# Top.net
KiCad netlist of a schematic drawn in Altium Designer
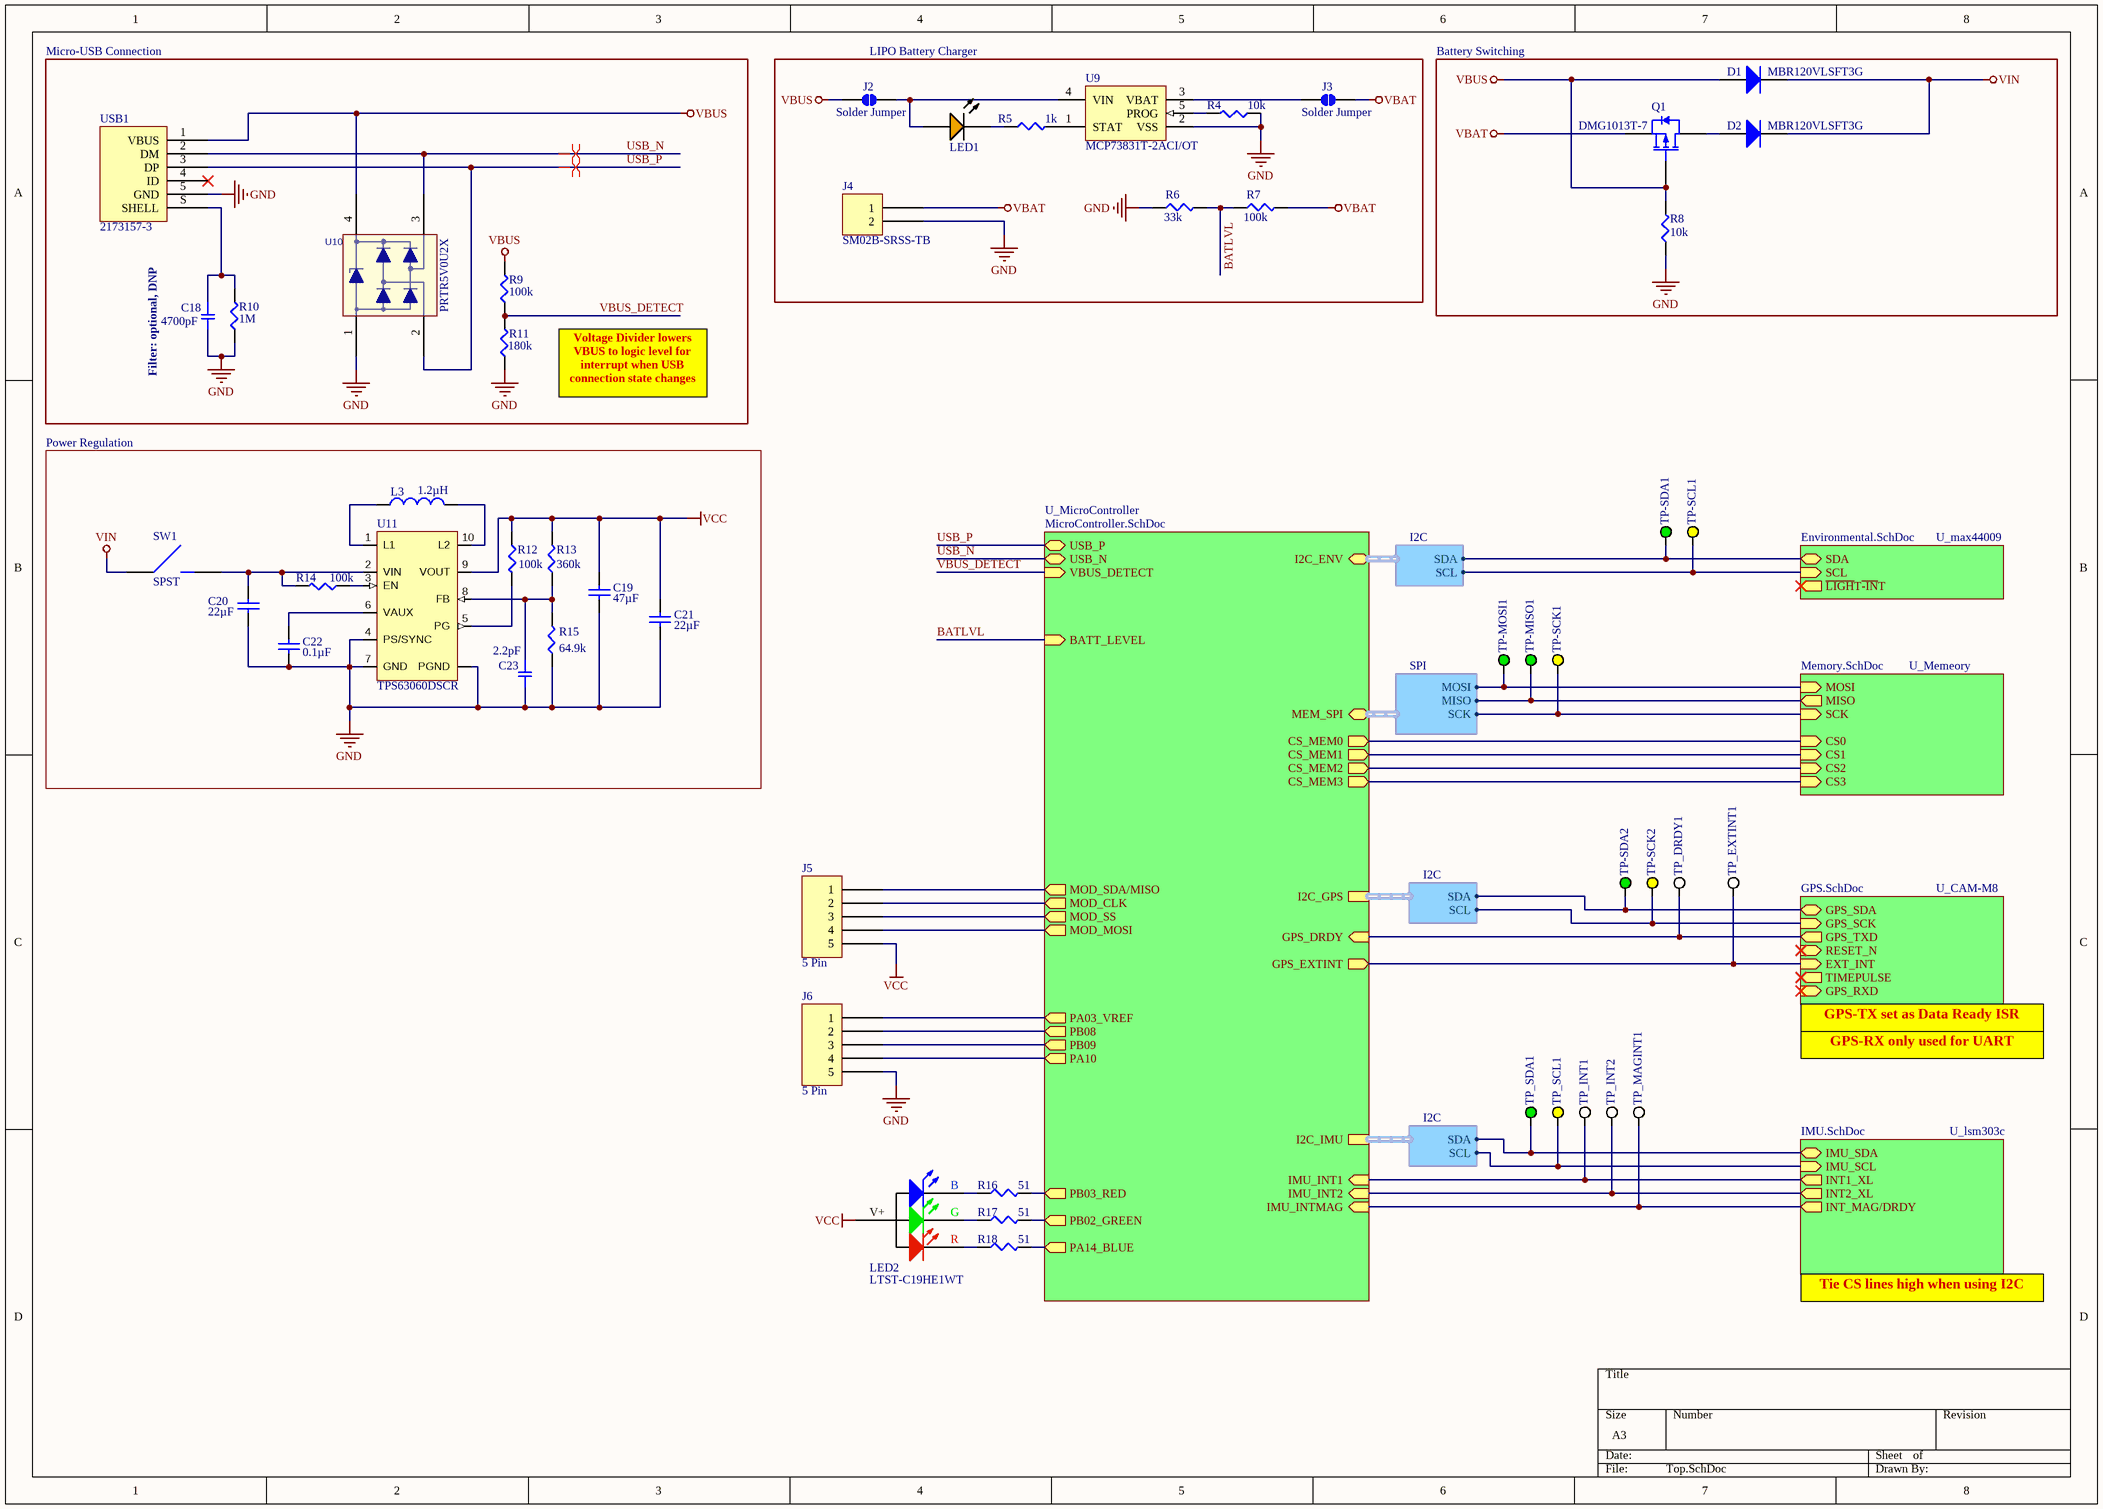
[diagram p0: Top.SchDoc]

(export (version "E")
  (design (tool "Eeschema 10.0.6"))
  (components
    (comp (ref "C18")
      (value "4700pF")
      (footprint "SMD-0603C")
      (description "CAP CER 4700PF 100V X7R 0603")
      (fields
        (field (name "DIGI-KEY PART NUMBER") "490-4930-1-ND")
        (field (name "PART NUMBER") "GCM188R72A472KA37D")
      )
      (libsource (lib "capacitor_murata_0603") (part "GCM188R72A472KA37D"))
    )
    (comp (ref "C19")
      (value "CL21A476MQCLRNC")
      (footprint "C0603N")
      (fields
        (field (name "HOUSEPART") "NO")
        (field (name "TOLERANCE") "±20%")
        (field (name "VOLTAGE") "6.3V")
        (field (name "CAPACITANCE") "47µF")
      )
      (libsource (lib "MF_Passives") (part "CAPACITOR_NP"))
    )
    (comp (ref "C20")
      (value "CL21A226MQCLQNC")
      (footprint "C0603N")
      (fields
        (field (name "HOUSEPART") "NO")
        (field (name "TOLERANCE") "±20%")
        (field (name "VOLTAGE") "6.3V")
        (field (name "CAPACITANCE") "22µF")
      )
      (libsource (lib "MF_Passives") (part "CAPACITOR_NP"))
    )
    (comp (ref "C21")
      (value "CL21A226MQCLQNC")
      (footprint "C0603N")
      (fields
        (field (name "HOUSEPART") "NO")
        (field (name "TOLERANCE") "±20%")
        (field (name "VOLTAGE") "6.3V")
        (field (name "CAPACITANCE") "22µF")
      )
      (libsource (lib "MF_Passives") (part "CAPACITOR_NP"))
    )
    (comp (ref "C22")
      (value "CL10B104KO8NFNC")
      (footprint "C0603N")
      (fields
        (field (name "HOUSEPART") "NO")
        (field (name "TOLERANCE") "±10%")
        (field (name "VOLTAGE") "16V")
        (field (name "CAPACITANCE") "0.1µF")
      )
      (libsource (lib "MF_Passives") (part "CAPACITOR_NP"))
    )
    (comp (ref "C23")
      (value "2.2pF")
      (footprint "SMD-0603C")
      (description "CAP CER 2.2PF 50V NP0 0603")
      (fields
        (field (name "DIGI-KEY PART NUMBER") "490-12719-1-ND")
        (field (name "PART NUMBER") "GRM1885C1H2R2BA01D")
      )
      (libsource (lib "capacitor_murata_0603") (part "GRM1885C1H2R2BA01D"))
    )
    (comp (ref "D1")
      (value "MBR120VLSFT3G")
      (footprint "MBR120VLSFT3G")
      (description "Diode Schottky 20V 1A Surface Mount SOD-123FL")
      (libsource (lib "OnSemi") (part "MBR120VLSFT3G"))
    )
    (comp (ref "D2")
      (value "MBR120VLSFT3G")
      (footprint "MBR120VLSFT3G")
      (description "Diode Schottky 20V 1A Surface Mount SOD-123FL")
      (libsource (lib "OnSemi") (part "MBR120VLSFT3G"))
    )
    (comp (ref "J2")
      (value "Solder Jumper")
      (footprint "Jumper_1.5x3")
      (libsource (lib "jumpers") (part "solderJumper"))
    )
    (comp (ref "J3")
      (value "Solder Jumper")
      (footprint "Jumper_1.5x3")
      (libsource (lib "jumpers") (part "solderJumper"))
    )
    (comp (ref "J4")
      (value "SM02B-SRSS-TB")
      (footprint "JST SM02B-SRSS-TB")
      (libsource (lib "Connectors") (part "2 Pin"))
    )
    (comp (ref "J5")
      (value "5 Pin")
      (footprint "PINHEAD127_1x5")
      (libsource (lib "Connectors") (part "5 Pin"))
    )
    (comp (ref "J6")
      (value "5 Pin")
      (footprint "PINHEAD127_1x5")
      (libsource (lib "Connectors") (part "5 Pin"))
    )
    (comp (ref "L3")
      (value "SRP4020-1R2M")
      (footprint "IND_BOURNS_SRP40")
      (fields (field (name "TOLERANCE") "±20%") (field (name "INDUCTANCE") "1.2µH"))
      (libsource (lib "Bourns") (part "SRP4020-1R2M"))
    )
    (comp (ref "LED1")
      (value "LTST-C190KFKT")
      (footprint "LED_0603")
      (description "LED Uni-Color Orange, 75 mW, 30 mA")
      (libsource (lib "Lite-On") (part "CMP-1544850-3"))
    )
    (comp (ref "LED2")
      (value "LTST-C19HE1WT")
      (footprint "LED_0606_160X160X35")
      (description "RGB LED 0606 (1616 metric)")
      (libsource (lib "Lite-On") (part "LTST-C19HE1WT"))
    )
    (comp (ref "Q1")
      (value "DMG1013T-7")
      (footprint "SOT50P175X90-3N")
      (description "P-Channel SOT-523")
      (libsource (lib "diodesInc") (part "DMG1013T-7c2930a883c7b1d54"))
    )
    (comp (ref "R4")
      (value "10k")
      (footprint "SMD-0603-RES")
      (description "RES SMD 10K OHM 1% 1/10W 0603")
      (fields
        (field (name "PART NUMBER") "ERJ-3EKF1002V")
        (field (name "DIGI-KEY PART NUMBER") "P10.0KHCT-ND")
      )
      (libsource (lib "Panasonic_ERJ_0603") (part "ERJ-3EKF1002V"))
    )
    (comp (ref "R5")
      (value "1k")
      (footprint "SMD-0603-RES")
      (description "RES SMD 1K OHM 1% 1/10W 0603")
      (fields
        (field (name "PART NUMBER") "ERJ-3EKF1001V")
        (field (name "DIGI-KEY PART NUMBER") "P1.00KHCT-ND")
      )
      (libsource (lib "Panasonic_ERJ_0603") (part "ERJ-3EKF1001V"))
    )
    (comp (ref "R6")
      (value "33k")
      (footprint "SMD-0603-RES")
      (description "RES SMD 33K OHM 1% 1/10W 0603")
      (fields
        (field (name "PART NUMBER") "ERJ-3EKF3302V")
        (field (name "DIGI-KEY PART NUMBER") "P33.0KHCT-ND")
      )
      (libsource (lib "Panasonic_ERJ_0603") (part "ERJ-3EKF3302V"))
    )
    (comp (ref "R7")
      (value "100k")
      (footprint "SMD-0603-RES")
      (description "RES SMD 100K OHM 1% 1/10W 0603")
      (fields
        (field (name "PART NUMBER") "ERJ-3EKF1003V")
        (field (name "DIGI-KEY PART NUMBER") "P100KHCT-ND")
      )
      (libsource (lib "Panasonic_ERJ_0603") (part "ERJ-3EKF1003V"))
    )
    (comp (ref "R8")
      (value "10k")
      (footprint "SMD-0603-RES")
      (description "RES SMD 10K OHM 1% 1/10W 0603")
      (fields
        (field (name "PART NUMBER") "ERJ-3EKF1002V")
        (field (name "DIGI-KEY PART NUMBER") "P10.0KHCT-ND")
      )
      (libsource (lib "Panasonic_ERJ_0603") (part "ERJ-3EKF1002V"))
    )
    (comp (ref "R9")
      (value "100k")
      (footprint "SMD-0603-RES")
      (description "RES SMD 100K OHM 1% 1/10W 0603")
      (fields
        (field (name "PART NUMBER") "ERJ-3EKF1003V")
        (field (name "DIGI-KEY PART NUMBER") "P100KHCT-ND")
      )
      (libsource (lib "Panasonic_ERJ_0603") (part "ERJ-3EKF1003V"))
    )
    (comp (ref "R10")
      (value "1M")
      (footprint "SMD-0603-RES")
      (description "RES SMD 1M OHM 1% 1/10W 0603")
      (fields
        (field (name "PART NUMBER") "ERJ-3EKF1004V")
        (field (name "DIGI-KEY PART NUMBER") "P1.00MHCT-ND")
      )
      (libsource (lib "Panasonic_ERJ_0603") (part "ERJ-3EKF1004V"))
    )
    (comp (ref "R11")
      (value "180k")
      (footprint "SMD-0603-RES")
      (description "RES SMD 180K OHM 1% 1/10W 0603")
      (fields
        (field (name "PART NUMBER") "ERJ-3EKF1803V")
        (field (name "DIGI-KEY PART NUMBER") "P180KHCT-ND")
      )
      (libsource (lib "Panasonic_ERJ_0603") (part "ERJ-3EKF1803V"))
    )
    (comp (ref "R12")
      (value "100k")
      (footprint "R0603N")
      (description "RES SMD 100K OHM 1% 1/10W 0603")
      (fields
        (field (name "PART NUMBER") "ERJ-3EKF1003V")
        (field (name "DIGI-KEY PART NUMBER") "P100KHCT-ND")
      )
      (libsource (lib "Panasonic_ERJ_0603") (part "ERJ-3EKF1003V"))
    )
    (comp (ref "R13")
      (value "360k")
      (footprint "SMD-0603-RES")
      (description "RES SMD 360K OHM 1% 1/10W 0603")
      (fields
        (field (name "PART NUMBER") "ERJ-3EKF3603V")
        (field (name "DIGI-KEY PART NUMBER") "P360KHCT-ND")
      )
      (libsource (lib "Panasonic_ERJ_0603") (part "ERJ-3EKF3603V"))
    )
    (comp (ref "R14")
      (value "100k")
      (footprint "R0603N")
      (description "RES SMD 100K OHM 1% 1/10W 0603")
      (fields
        (field (name "PART NUMBER") "ERJ-3EKF1003V")
        (field (name "DIGI-KEY PART NUMBER") "P100KHCT-ND")
      )
      (libsource (lib "Panasonic_ERJ_0603") (part "ERJ-3EKF1003V"))
    )
    (comp (ref "R15")
      (value "64.9k")
      (footprint "SMD-0603-RES")
      (description "RES SMD 64.9K OHM 1% 1/10W 0603")
      (fields
        (field (name "PART NUMBER") "ERJ-3EKF6492V")
        (field (name "DIGI-KEY PART NUMBER") "P64.9KHCT-ND")
      )
      (libsource (lib "Panasonic_ERJ_0603") (part "ERJ-3EKF6492V"))
    )
    (comp (ref "R16")
      (value "51")
      (footprint "SMD-0603-RES")
      (description "RES SMD 51 OHM 1% 1/10W 0603")
      (fields
        (field (name "PART NUMBER") "ERJ-3EKF51R0V")
        (field (name "DIGI-KEY PART NUMBER") "P51.0HCT-ND")
      )
      (libsource (lib "Panasonic_ERJ_0603") (part "ERJ-3EKF51R0V"))
    )
    (comp (ref "R17")
      (value "51")
      (footprint "SMD-0603-RES")
      (description "RES SMD 51 OHM 1% 1/10W 0603")
      (fields
        (field (name "PART NUMBER") "ERJ-3EKF51R0V")
        (field (name "DIGI-KEY PART NUMBER") "P51.0HCT-ND")
      )
      (libsource (lib "Panasonic_ERJ_0603") (part "ERJ-3EKF51R0V"))
    )
    (comp (ref "R18")
      (value "51")
      (footprint "SMD-0603-RES")
      (description "RES SMD 51 OHM 1% 1/10W 0603")
      (fields
        (field (name "PART NUMBER") "ERJ-3EKF51R0V")
        (field (name "DIGI-KEY PART NUMBER") "P51.0HCT-ND")
      )
      (libsource (lib "Panasonic_ERJ_0603") (part "ERJ-3EKF51R0V"))
    )
    (comp (ref "SW1")
      (value "SPST")
      (footprint "PINHEAD254_1x2")
      (description "SPST Switch")
      (libsource (lib "mechanical") (part "SPST switch"))
    )
    (comp (ref "TP-MISO1")
      (value "Test Point")
      (footprint "tp_30mil")
      (description "Test Point Green")
      (libsource (lib "jumpers") (part "testpoint_green"))
    )
    (comp (ref "TP-MOSI1")
      (value "Test Point")
      (footprint "tp_30mil")
      (description "Test Point Green")
      (libsource (lib "jumpers") (part "testpoint_green"))
    )
    (comp (ref "TP-SCK1")
      (value "Test Point")
      (footprint "tp_30mil")
      (description "Test Point Yellow")
      (libsource (lib "jumpers") (part "testpoint_yellow"))
    )
    (comp (ref "TP-SCK2")
      (value "Test Point")
      (footprint "tp_30mil")
      (description "Test Point Yellow")
      (libsource (lib "jumpers") (part "testpoint_yellow"))
    )
    (comp (ref "TP-SCL1")
      (value "Test Point")
      (footprint "tp_30mil")
      (description "Test Point Yellow")
      (libsource (lib "jumpers") (part "testpoint_yellow"))
    )
    (comp (ref "TP-SDA1")
      (value "Test Point")
      (footprint "tp_30mil")
      (description "Test Point Green")
      (libsource (lib "jumpers") (part "testpoint_green"))
    )
    (comp (ref "TP-SDA2")
      (value "Test Point")
      (footprint "tp_30mil")
      (description "Test Point Green")
      (libsource (lib "jumpers") (part "testpoint_green"))
    )
    (comp (ref "TP_DRDY1")
      (value "Test Point")
      (footprint "tp_30mil")
      (description "Test Point White")
      (libsource (lib "jumpers") (part "testpoint_white"))
    )
    (comp (ref "TP_EXTINT1")
      (value "Test Point")
      (footprint "tp_30mil")
      (description "Test Point White")
      (libsource (lib "jumpers") (part "testpoint_white"))
    )
    (comp (ref "TP_INT1")
      (value "Test Point")
      (footprint "tp_30mil")
      (description "Test Point White")
      (libsource (lib "jumpers") (part "testpoint_white"))
    )
    (comp (ref "TP_INT2")
      (value "Test Point")
      (footprint "tp_30mil")
      (description "Test Point White")
      (libsource (lib "jumpers") (part "testpoint_white"))
    )
    (comp (ref "TP_MAGINT1")
      (value "Test Point")
      (footprint "tp_30mil")
      (description "Test Point White")
      (libsource (lib "jumpers") (part "testpoint_white"))
    )
    (comp (ref "TP_SCL1")
      (value "Test Point")
      (footprint "tp_30mil")
      (description "Test Point Yellow")
      (libsource (lib "jumpers") (part "testpoint_yellow"))
    )
    (comp (ref "TP_SDA1")
      (value "Test Point")
      (footprint "tp_30mil")
      (description "Test Point Green")
      (libsource (lib "jumpers") (part "testpoint_green"))
    )
    (comp (ref "U9")
      (value "MCP73831T-2ACI/OT")
      (footprint "SOT-23-5_MC")
      (description "MCP73831 Series Single-Cell Li-Ion/Li-Polymer Battery Charge Controller SOT-23-5")
      (libsource (lib "Microchip") (part "MCHP-MCP73831T-5"))
    )
    (comp (ref "U10")
      (value "PRTR5V0U2X")
      (footprint "SOT143B")
      (libsource (lib "PRTR5V0U2X") (part "PRTR5V0U2X"))
    )
    (comp (ref "U11")
      (value "TPS63060DSCR")
      (footprint "TI_DRC_S-PVSON-N10")
      (libsource (lib "TPS63060DSCR") (part "TPS63060DSCR"))
    )
    (comp (ref "USB1")
      (value "2173157-3")
      (footprint "CONN_2173157")
      (description "Conn Micro USB 2.0 Type B Splash Proof")
      (libsource (lib "2173157-3") (part "USB-CONN-2173157-3"))
    )
  )
  (nets
    (net (code "3") (name "/BATLVL") (class "Default")
      (node (ref "R6") (pin "2") (pinfunction "2_2") (pintype "passive"))
      (node (ref "R7") (pin "1") (pinfunction "1_1") (pintype "passive"))
    )
    (net (code "8") (name "/GPS_EXTINT") (class "Default")
      (node (ref "TP_EXTINT1") (pin "1") (pinfunction "1_1") (pintype "passive"))
    )
    (net (code "10") (name "/GPS_SCK") (class "Default")
      (node (ref "TP-SCK2") (pin "1") (pinfunction "1_1") (pintype "passive"))
    )
    (net (code "11") (name "/GPS_SDA") (class "Default")
      (node (ref "TP-SDA2") (pin "1") (pinfunction "1_1") (pintype "passive"))
    )
    (net (code "12") (name "/GPS_TXD") (class "Default")
      (node (ref "TP_DRDY1") (pin "1") (pinfunction "1_1") (pintype "passive"))
    )
    (net (code "13") (name "/IMU_SCL") (class "Default")
      (node (ref "TP_SCL1") (pin "1") (pinfunction "1_1") (pintype "passive"))
    )
    (net (code "14") (name "/IMU_SDA") (class "Default")
      (node (ref "TP_SDA1") (pin "1") (pinfunction "1_1") (pintype "passive"))
    )
    (net (code "15") (name "/INT1_XL") (class "Default")
      (node (ref "TP_INT1") (pin "1") (pinfunction "1_1") (pintype "passive"))
    )
    (net (code "16") (name "/INT2_XL") (class "Default")
      (node (ref "TP_INT2") (pin "1") (pinfunction "1_1") (pintype "passive"))
    )
    (net (code "17") (name "/INT_MAG{slash}DRDY") (class "Default")
      (node (ref "TP_MAGINT1") (pin "1") (pinfunction "1_1") (pintype "passive"))
    )
    (net (code "18") (name "/MISO") (class "Default")
      (node (ref "TP-MISO1") (pin "1") (pinfunction "1_1") (pintype "passive"))
    )
    (net (code "19") (name "/MOD_CLK") (class "Default")
      (node (ref "J5") (pin "2") (pinfunction "2_2") (pintype "passive"))
    )
    (net (code "20") (name "/MOD_MOSI") (class "Default")
      (node (ref "J5") (pin "4") (pinfunction "4_4") (pintype "passive"))
    )
    (net (code "21") (name "/MOD_SDA{slash}MISO") (class "Default")
      (node (ref "J5") (pin "1") (pinfunction "1_1") (pintype "passive"))
    )
    (net (code "22") (name "/MOD_SS") (class "Default")
      (node (ref "J5") (pin "3") (pinfunction "3_3") (pintype "passive"))
    )
    (net (code "23") (name "/MOSI") (class "Default")
      (node (ref "TP-MOSI1") (pin "1") (pinfunction "1_1") (pintype "passive"))
    )
    (net (code "24") (name "/PA03_VREF") (class "Default")
      (node (ref "J6") (pin "1") (pinfunction "1_1") (pintype "passive"))
    )
    (net (code "25") (name "/PA10") (class "Default")
      (node (ref "J6") (pin "4") (pinfunction "4_4") (pintype "passive"))
    )
    (net (code "26") (name "/PA14_BLUE") (class "Default")
      (node (ref "R18") (pin "2") (pinfunction "2_2") (pintype "passive"))
    )
    (net (code "27") (name "/PB02_GREEN") (class "Default")
      (node (ref "R17") (pin "2") (pinfunction "2_2") (pintype "passive"))
    )
    (net (code "28") (name "/PB03_RED") (class "Default")
      (node (ref "R16") (pin "2") (pinfunction "2_2") (pintype "passive"))
    )
    (net (code "29") (name "/PB08") (class "Default")
      (node (ref "J6") (pin "2") (pinfunction "2_2") (pintype "passive"))
    )
    (net (code "30") (name "/PB09") (class "Default")
      (node (ref "J6") (pin "3") (pinfunction "3_3") (pintype "passive"))
    )
    (net (code "32") (name "/SCK") (class "Default")
      (node (ref "TP-SCK1") (pin "1") (pinfunction "1_1") (pintype "passive"))
    )
    (net (code "33") (name "/SCL") (class "Default")
      (node (ref "TP-SCL1") (pin "1") (pinfunction "1_1") (pintype "passive"))
    )
    (net (code "34") (name "/SDA") (class "Default")
      (node (ref "TP-SDA1") (pin "1") (pinfunction "1_1") (pintype "passive"))
    )
    (net (code "36") (name "/USB_N") (class "Default")
      (node (ref "U10") (pin "3") (pinfunction "I/O2_3") (pintype "passive"))
      (node (ref "USB1") (pin "2") (pinfunction "DM_2") (pintype "passive"))
    )
    (net (code "37") (name "/USB_P") (class "Default")
      (node (ref "U10") (pin "2") (pinfunction "I/O1_2") (pintype "passive"))
      (node (ref "USB1") (pin "3") (pinfunction "DP_3") (pintype "passive"))
    )
    (net (code "38") (name "/VBUS_DETECT") (class "Default")
      (node (ref "R11") (pin "2") (pinfunction "2_2") (pintype "passive"))
      (node (ref "R9") (pin "1") (pinfunction "1_1") (pintype "passive"))
    )
    (net (code "42") (name "GND") (class "Default")
      (node (ref "C18") (pin "2") (pinfunction "2_2") (pintype "passive"))
      (node (ref "C19") (pin "2") (pinfunction "2_2") (pintype "passive"))
      (node (ref "C20") (pin "2") (pinfunction "2_2") (pintype "passive"))
      (node (ref "C21") (pin "2") (pinfunction "2_2") (pintype "passive"))
      (node (ref "C22") (pin "2") (pinfunction "2_2") (pintype "passive"))
      (node (ref "C23") (pin "2") (pinfunction "2_2") (pintype "passive"))
      (node (ref "J4") (pin "2") (pinfunction "2_2") (pintype "passive"))
      (node (ref "J6") (pin "5") (pinfunction "5_5") (pintype "passive"))
      (node (ref "R10") (pin "1") (pinfunction "1_1") (pintype "passive"))
      (node (ref "R11") (pin "1") (pinfunction "1_1") (pintype "passive"))
      (node (ref "R15") (pin "1") (pinfunction "1_1") (pintype "passive"))
      (node (ref "R4") (pin "1") (pinfunction "1_1") (pintype "passive"))
      (node (ref "R6") (pin "1") (pinfunction "1_1") (pintype "passive"))
      (node (ref "R8") (pin "1") (pinfunction "1_1") (pintype "passive"))
      (node (ref "U10") (pin "1") (pinfunction "GND_1") (pintype "passive"))
      (node (ref "U11") (pin "11") (pinfunction "PGND_11") (pintype "passive"))
      (node (ref "U11") (pin "4") (pinfunction "PS/SYNC_4") (pintype "passive"))
      (node (ref "U11") (pin "7") (pinfunction "GND_7") (pintype "power_in"))
      (node (ref "U9") (pin "2") (pinfunction "VSS_2") (pintype "power_in"))
      (node (ref "USB1") (pin "5") (pinfunction "GND_5") (pintype "passive"))
    )
    (net (code "43") (name "Net-(D2-A)") (class "Default")
      (node (ref "D2") (pin "1") (pinfunction "A_1") (pintype "passive"))
      (node (ref "Q1") (pin "3") (pinfunction "D_3") (pintype "passive"))
    )
    (net (code "44") (name "Net-(LED1-A)") (class "Default")
      (node (ref "J2") (pin "2") (pinfunction "2_2") (pintype "passive"))
      (node (ref "LED1") (pin "1") (pinfunction "A_1") (pintype "passive"))
      (node (ref "U9") (pin "4") (pinfunction "VIN_4") (pintype "power_in"))
    )
    (net (code "45") (name "Net-(LED1-K)") (class "Default")
      (node (ref "LED1") (pin "2") (pinfunction "K_2") (pintype "passive"))
      (node (ref "R5") (pin "1") (pinfunction "1_1") (pintype "passive"))
    )
    (net (code "46") (name "Net-(LED2-B)") (class "Default")
      (node (ref "LED2") (pin "3") (pinfunction "B_3") (pintype "passive"))
      (node (ref "R16") (pin "1") (pinfunction "1_1") (pintype "passive"))
    )
    (net (code "47") (name "Net-(LED2-G)") (class "Default")
      (node (ref "LED2") (pin "2") (pinfunction "G_2") (pintype "passive"))
      (node (ref "R17") (pin "1") (pinfunction "1_1") (pintype "passive"))
    )
    (net (code "48") (name "Net-(LED2-R)") (class "Default")
      (node (ref "LED2") (pin "1") (pinfunction "R_1") (pintype "passive"))
      (node (ref "R18") (pin "1") (pinfunction "1_1") (pintype "passive"))
    )
    (net (code "49") (name "Net-(U9-PROG)") (class "Default")
      (node (ref "R4") (pin "2") (pinfunction "2_2") (pintype "passive"))
      (node (ref "U9") (pin "5") (pinfunction "PROG_5") (pintype "input"))
    )
    (net (code "50") (name "Net-(U9-STAT)") (class "Default")
      (node (ref "R5") (pin "2") (pinfunction "2_2") (pintype "passive"))
      (node (ref "U9") (pin "1") (pinfunction "STAT_1") (pintype "tri_state"))
    )
    (net (code "51") (name "Net-(U9-VBAT)") (class "Default")
      (node (ref "J3") (pin "1") (pinfunction "1_1") (pintype "passive"))
      (node (ref "U9") (pin "3") (pinfunction "VBAT_3") (pintype "power_in"))
    )
    (net (code "52") (name "Net-(U11-EN)") (class "Default")
      (node (ref "R14") (pin "1") (pinfunction "1_1") (pintype "passive"))
      (node (ref "U11") (pin "3") (pinfunction "EN_3") (pintype "input"))
    )
    (net (code "53") (name "Net-(U11-FB)") (class "Default")
      (node (ref "C23") (pin "1") (pinfunction "1_1") (pintype "passive"))
      (node (ref "R13") (pin "1") (pinfunction "1_1") (pintype "passive"))
      (node (ref "R15") (pin "2") (pinfunction "2_2") (pintype "passive"))
      (node (ref "U11") (pin "8") (pinfunction "FB_8") (pintype "input"))
    )
    (net (code "54") (name "Net-(U11-L1)") (class "Default")
      (node (ref "L3") (pin "1") (pinfunction "1_1") (pintype "passive"))
      (node (ref "U11") (pin "1") (pinfunction "L1_1") (pintype "passive"))
    )
    (net (code "55") (name "Net-(U11-L2)") (class "Default")
      (node (ref "L3") (pin "2") (pinfunction "2_2") (pintype "passive"))
      (node (ref "U11") (pin "10") (pinfunction "L2_10") (pintype "passive"))
    )
    (net (code "56") (name "Net-(U11-PG)") (class "Default")
      (node (ref "R12") (pin "2") (pinfunction "2_2") (pintype "passive"))
      (node (ref "U11") (pin "5") (pinfunction "PG_5") (pintype "output"))
    )
    (net (code "57") (name "Net-(U11-VAUX)") (class "Default")
      (node (ref "C22") (pin "1") (pinfunction "1_1") (pintype "passive"))
      (node (ref "U11") (pin "6") (pinfunction "VAUX_6") (pintype "passive"))
    )
    (net (code "58") (name "Net-(U11-VIN)") (class "Default")
      (node (ref "C20") (pin "1") (pinfunction "1_1") (pintype "passive"))
      (node (ref "R14") (pin "2") (pinfunction "2_2") (pintype "passive"))
      (node (ref "SW1") (pin "2") (pinfunction "2_2") (pintype "passive"))
      (node (ref "U11") (pin "2") (pinfunction "VIN_2") (pintype "power_in"))
    )
    (net (code "59") (name "Net-(USB1-SHELL)") (class "Default")
      (node (ref "C18") (pin "1") (pinfunction "1_1") (pintype "passive"))
      (node (ref "R10") (pin "2") (pinfunction "2_2") (pintype "passive"))
      (node (ref "USB1") (pin "S") (pinfunction "SHELL_S") (pintype "passive"))
    )
    (net (code "60") (name "VBAT") (class "Default")
      (node (ref "J3") (pin "2") (pinfunction "2_2") (pintype "passive"))
      (node (ref "J4") (pin "1") (pinfunction "1_1") (pintype "passive"))
      (node (ref "Q1") (pin "2") (pinfunction "S_2") (pintype "passive"))
      (node (ref "R7") (pin "2") (pinfunction "2_2") (pintype "passive"))
    )
    (net (code "61") (name "VBUS") (class "Default")
      (node (ref "D1") (pin "1") (pinfunction "A_1") (pintype "passive"))
      (node (ref "J2") (pin "1") (pinfunction "1_1") (pintype "passive"))
      (node (ref "Q1") (pin "1") (pinfunction "G_1") (pintype "passive"))
      (node (ref "R8") (pin "2") (pinfunction "2_2") (pintype "passive"))
      (node (ref "R9") (pin "2") (pinfunction "2_2") (pintype "passive"))
      (node (ref "U10") (pin "4") (pinfunction "VCC_4") (pintype "passive"))
      (node (ref "USB1") (pin "1") (pinfunction "VBUS_1") (pintype "passive"))
    )
    (net (code "62") (name "VCC") (class "Default")
      (node (ref "C19") (pin "1") (pinfunction "1_1") (pintype "passive"))
      (node (ref "C21") (pin "1") (pinfunction "1_1") (pintype "passive"))
      (node (ref "J5") (pin "5") (pinfunction "5_5") (pintype "passive"))
      (node (ref "LED2") (pin "4") (pinfunction "A_4") (pintype "passive"))
      (node (ref "R12") (pin "1") (pinfunction "1_1") (pintype "passive"))
      (node (ref "R13") (pin "2") (pinfunction "2_2") (pintype "passive"))
      (node (ref "U11") (pin "9") (pinfunction "VOUT_9") (pintype "power_in"))
    )
    (net (code "63") (name "VIN") (class "Default")
      (node (ref "D1") (pin "2") (pinfunction "K_2") (pintype "passive"))
      (node (ref "D2") (pin "2") (pinfunction "K_2") (pintype "passive"))
      (node (ref "SW1") (pin "1") (pinfunction "1_1") (pintype "passive"))
    )
    (net (code "64") (name "unconnected-(USB1-ID-Pad4)") (class "Default")
      (node (ref "USB1") (pin "4") (pinfunction "ID_4") (pintype "passive+no_connect"))
    )
  )
)
